# PAGE2_-_MCU.net
KiCad netlist of a schematic drawn in Altium Designer
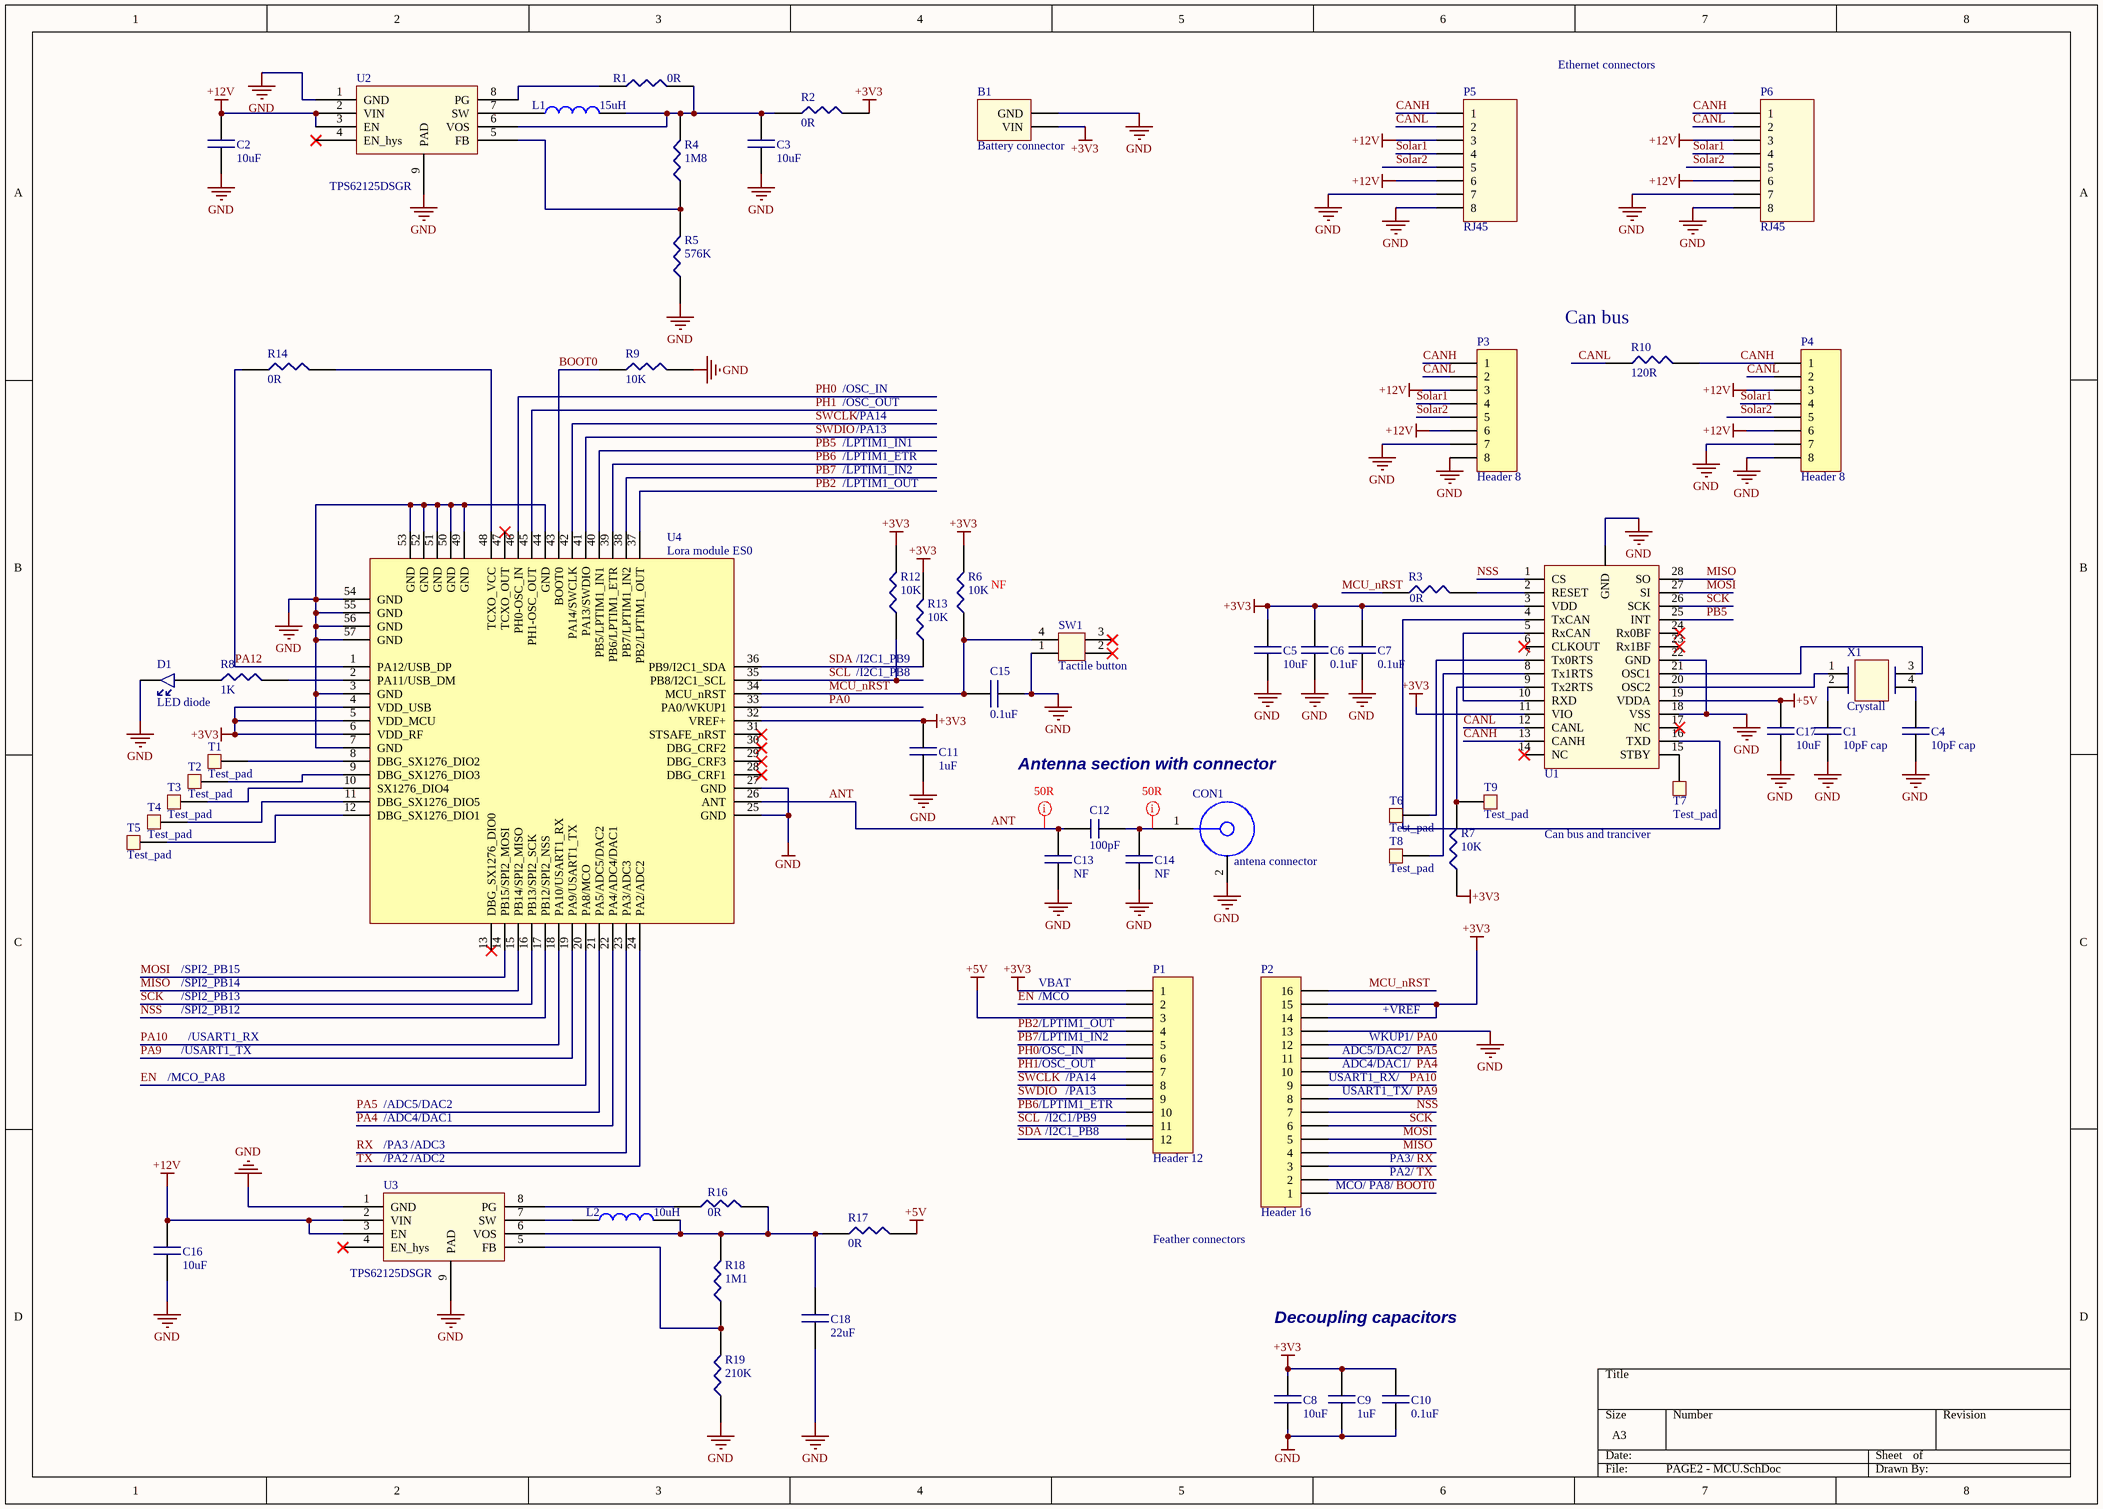
[diagram p0: PAGE2 - MCU.SchDoc]

(export (version "E")
  (design (tool "Eeschema 10.0.6"))
  (components
    (comp (ref "B1")
      (value "Battery connector")
      (footprint "BAT_CON")
      (description "JST-PH 2-Pin SMT Right Angle Breakout Board")
      (fields
        (field (name "MANUFACTURER") "Adafruit Industries")
        (field (name "MANUFACTURER PART NUMBER") "1862")
      )
      (libsource (lib "Lora_feather") (part "1862"))
    )
    (comp (ref "C1")
      (value "10pF cap")
      (footprint "0603Cap")
      (description "Cap Ceramic 10pF 50V X7R 10% SMD 0603 125C T/R")
      (fields
        (field (name "MANUFACTURER") "Kyocera AVX")
        (field (name "MANUFACTURER PART NUMBER") "06035C100KAT2A")
      )
      (libsource (lib "Lora_feather") (part "10pF"))
    )
    (comp (ref "C2")
      (value "10uF")
      (footprint "Lora_feather:0603Cap")
      (fields
        (field (name "MANUFACTURER") "Murata")
        (field (name "MANUFACTURER PART NUMBER") "ZRB18AR61E106ME01L")
        (field (name "TOLERANCE") "±20%")
      )
      (libsource (lib "Lora_feather") (part "10uF Cap"))
    )
    (comp (ref "C3")
      (value "10uF")
      (footprint "Lora_feather:0603Cap")
      (fields
        (field (name "MANUFACTURER") "Murata")
        (field (name "MANUFACTURER PART NUMBER") "ZRB18AR61E106ME01L")
        (field (name "TOLERANCE") "±20%")
      )
      (libsource (lib "Lora_feather") (part "10uF Cap"))
    )
    (comp (ref "C4")
      (value "10pF cap")
      (footprint "0603Cap")
      (description "Cap Ceramic 10pF 50V X7R 10% SMD 0603 125C T/R")
      (fields
        (field (name "MANUFACTURER") "Kyocera AVX")
        (field (name "MANUFACTURER PART NUMBER") "06035C100KAT2A")
      )
      (libsource (lib "Lora_feather") (part "10pF"))
    )
    (comp (ref "C5")
      (value "10uF")
      (footprint "Lora_feather:0603Cap")
      (fields
        (field (name "MANUFACTURER") "Murata")
        (field (name "MANUFACTURER PART NUMBER") "ZRB18AR61E106ME01L")
        (field (name "TOLERANCE") "±20%")
      )
      (libsource (lib "Lora_feather") (part "10uF Cap"))
    )
    (comp (ref "C6")
      (value "0.1uF")
      (footprint "Lora_feather:0603Cap")
      (description "Multilayer Ceramic Capacitors MLCC - SMD/SMT .1uF 50Volts X7R +/-10% 0603 STD")
      (fields
        (field (name "MANUFACTURER") "KEMET")
        (field (name "MANUFACTURER PART NUMBER") "C0603C104K4RAC7081")
      )
      (libsource (lib "Lora_feather") (part "0.1uF"))
    )
    (comp (ref "C7")
      (value "0.1uF")
      (footprint "Lora_feather:0603Cap")
      (description "Multilayer Ceramic Capacitors MLCC - SMD/SMT .1uF 50Volts X7R +/-10% 0603 STD")
      (fields
        (field (name "MANUFACTURER") "KEMET")
        (field (name "MANUFACTURER PART NUMBER") "C0603C104K4RAC7081")
      )
      (libsource (lib "Lora_feather") (part "0.1uF"))
    )
    (comp (ref "C8")
      (value "10uF")
      (footprint "Lora_feather:0603Cap")
      (fields
        (field (name "MANUFACTURER") "Murata")
        (field (name "MANUFACTURER PART NUMBER") "ZRB18AR61E106ME01L")
        (field (name "TOLERANCE") "±20%")
      )
      (libsource (lib "Lora_feather") (part "10uF Cap"))
    )
    (comp (ref "C9")
      (value "1uF")
      (footprint "Lora_feather:0603Cap")
      (description "1µF 50V Ceramic Capacitor X5R 0603 (1608 Metric) 0.063\" L x 0.031\" W (1.60mm x 0.80mm)")
      (fields
        (field (name "MANUFACTURER") "TDK")
        (field (name "MANUFACTURER PART NUMBER") "C1608X5R1E105K080AC")
      )
      (libsource (lib "Lora_feather") (part "1uF"))
    )
    (comp (ref "C10")
      (value "0.1uF")
      (footprint "Lora_feather:0603Cap")
      (description "Multilayer Ceramic Capacitors MLCC - SMD/SMT .1uF 50Volts X7R +/-10% 0603 STD")
      (fields
        (field (name "MANUFACTURER") "KEMET")
        (field (name "MANUFACTURER PART NUMBER") "C0603C104K4RAC7081")
      )
      (libsource (lib "Lora_feather") (part "0.1uF"))
    )
    (comp (ref "C11")
      (value "1uF")
      (footprint "Lora_feather:0603Cap")
      (description "1µF 50V Ceramic Capacitor X5R 0603 (1608 Metric) 0.063\" L x 0.031\" W (1.60mm x 0.80mm)")
      (fields
        (field (name "MANUFACTURER") "TDK")
        (field (name "MANUFACTURER PART NUMBER") "C1608X5R1E105K080AC")
      )
      (libsource (lib "Lora_feather") (part "1uF"))
    )
    (comp (ref "C12")
      (value "100pF")
      (footprint "0402CAP")
      (fields
        (field (name "MANUFACTURER") "Multicomp")
        (field (name "MANUFACTURER PART NUMBER") "MC0402B101K500CT")
      )
      (libsource (lib "Lora_feather") (part "0F"))
    )
    (comp (ref "C13") (value "NF") (footprint "0402CAP") (libsource (lib "Lora_feather") (part "Cap0402")))
    (comp (ref "C14") (value "NF") (footprint "0402CAP") (libsource (lib "Lora_feather") (part "Cap0402")))
    (comp (ref "C15")
      (value "0.1uF")
      (footprint "Lora_feather:0603Cap")
      (description "Multilayer Ceramic Capacitors MLCC - SMD/SMT .1uF 50Volts X7R +/-10% 0603 STD")
      (fields
        (field (name "MANUFACTURER") "KEMET")
        (field (name "MANUFACTURER PART NUMBER") "C0603C104K4RAC7081")
      )
      (libsource (lib "Lora_feather") (part "0.1uF"))
    )
    (comp (ref "C16")
      (value "10uF")
      (footprint "Lora_feather:0603Cap")
      (fields
        (field (name "MANUFACTURER") "Murata")
        (field (name "MANUFACTURER PART NUMBER") "ZRB18AR61E106ME01L")
        (field (name "TOLERANCE") "±20%")
      )
      (libsource (lib "Lora_feather") (part "10uF Cap"))
    )
    (comp (ref "C17")
      (value "10uF")
      (footprint "Lora_feather:0603Cap")
      (fields
        (field (name "MANUFACTURER") "Murata")
        (field (name "MANUFACTURER PART NUMBER") "ZRB18AR61E106ME01L")
        (field (name "TOLERANCE") "±20%")
      )
      (libsource (lib "Lora_feather") (part "10uF Cap"))
    )
    (comp (ref "C18")
      (value "22uF")
      (footprint "0603Cap")
      (fields
        (field (name "MANUFACTURER") "Murata")
        (field (name "MANUFACTURER PART NUMBER") "ZRB18AR60J226ME01L")
        (field (name "TOLERANCE") "±20%")
      )
      (libsource (lib "Lora_feather") (part "22uF"))
    )
    (comp (ref "CON1")
      (value "antena connector")
      (footprint "Lora_feather:uFL SMD CONNECTOR")
      (description "CONN UMC JACK STR 50 OHM SMD")
      (fields
        (field (name "MANUFACTURER") "Hirose")
        (field (name "MANUFACTURER PART NUMBER") "U.FL-R-SMT-1(10)")
      )
      (libsource (lib "Lora_feather") (part "U.FL-R-SMT-1(10)"))
    )
    (comp (ref "D1")
      (value "LED diode")
      (footprint "LED")
      (fields
        (field (name "MANUFACTURER") "Kingbright")
        (field (name "MANUFACTURER PART NUMBER") "KPG1-1608VGC-TT-5MAV")
      )
      (libsource (lib "Lora_feather") (part "LED"))
    )
    (comp (ref "L1")
      (value "15uH")
      (footprint "Lora_feather:Inductor 3.0x2.5")
      (description "Fixed Inductors 15uH 0.28ohms 0.56A")
      (fields
        (field (name "MANUFACTURER") "TDK")
        (field (name "MANUFACTURER PART NUMBER") "VLF302515MT-150M")
      )
      (libsource (lib "Lora_feather") (part "15uH inductor"))
    )
    (comp (ref "L2")
      (value "10uH")
      (footprint "Inductor 3.0x2.5")
      (description "COILCRAFT   LPS3314-103MRB   INDUCTOR, SHLD, 10UH, 20%, 0.65A, SMD")
      (fields
        (field (name "MANUFACTURER") "Coilcraft")
        (field (name "MANUFACTURER PART NUMBER") "LPS3314-103MRB")
      )
      (libsource (lib "Lora_feather") (part "10uH"))
    )
    (comp (ref "P1")
      (value "Header 12")
      (footprint "HDR1X12")
      (description "Header, 12-Pin")
      (fields (field (name "PUBLISHER") "Altium Limited"))
      (libsource (lib "Miscellaneous Connectors") (part "Header 12"))
    )
    (comp (ref "P2")
      (value "Header 16")
      (footprint "HDR1X16")
      (description "Header, 16-Pin")
      (fields (field (name "PUBLISHER") "Altium Limited"))
      (libsource (lib "Miscellaneous Connectors") (part "Header 16"))
    )
    (comp (ref "P3")
      (value "Header 8")
      (footprint "HDR1X8")
      (description "Header, 8-Pin")
      (fields (field (name "PUBLISHER") "Altium Limited"))
      (libsource (lib "Miscellaneous Connectors") (part "Header 8"))
    )
    (comp (ref "P4")
      (value "Header 8")
      (footprint "HDR1X8")
      (description "Header, 8-Pin")
      (fields (field (name "PUBLISHER") "Altium Limited"))
      (libsource (lib "Miscellaneous Connectors") (part "Header 8"))
    )
    (comp (ref "P5")
      (value "RJ45")
      (footprint "EThernet conn")
      (description "MODULAR JACK")
      (fields (field (name "MANUFACTURER") "Molex") (field (name "MANUFACTURER PART NUMBER") "44620-0001"))
      (libsource (lib "Lora_feather") (part "44620-0001"))
    )
    (comp (ref "P6")
      (value "RJ45")
      (footprint "EThernet conn")
      (description "MODULAR JACK")
      (fields (field (name "MANUFACTURER") "Molex") (field (name "MANUFACTURER PART NUMBER") "44620-0001"))
      (libsource (lib "Lora_feather") (part "44620-0001"))
    )
    (comp (ref "R1")
      (value "0R")
      (footprint "Lora_feather:0603Res")
      (description "RES SMD 0.0OHM JUMPER 1/10W 0603")
      (fields
        (field (name "MANUFACTURER") "Vishay")
        (field (name "MANUFACTURER PART NUMBER") "CRCW06030000Z0EA")
      )
      (libsource (lib "Lora_feather") (part "0R"))
    )
    (comp (ref "R2")
      (value "0R")
      (footprint "Lora_feather:0603Res")
      (description "RES SMD 0.0OHM JUMPER 1/10W 0603")
      (fields
        (field (name "MANUFACTURER") "Vishay")
        (field (name "MANUFACTURER PART NUMBER") "CRCW06030000Z0EA")
      )
      (libsource (lib "Lora_feather") (part "0R"))
    )
    (comp (ref "R3")
      (value "0R")
      (footprint "Lora_feather:0603Res")
      (description "RES SMD 0.0OHM JUMPER 1/10W 0603")
      (fields
        (field (name "MANUFACTURER") "Vishay")
        (field (name "MANUFACTURER PART NUMBER") "CRCW06030000Z0EA")
      )
      (libsource (lib "Lora_feather") (part "0R"))
    )
    (comp (ref "R4")
      (value "1M8")
      (footprint "Lora_feather:0603Res")
      (fields
        (field (name "MANUFACTURER") "Multicomp")
        (field (name "MANUFACTURER PART NUMBER") "MCHVR03FTFX1804")
      )
      (libsource (lib "Lora_feather") (part "1.8Mohm Res"))
    )
    (comp (ref "R5")
      (value "576K")
      (footprint "Lora_feather:0603Res")
      (description "Res Thick Film 0603 576K Ohm 1% 0.1W(1/10W) ±100ppm/C Molded SMD Automotive Punched T/R")
      (fields
        (field (name "MANUFACTURER") "Panasonic")
        (field (name "MANUFACTURER PART NUMBER") "ERJ-3EKF5763V")
      )
      (libsource (lib "Lora_feather") (part "576K Res"))
    )
    (comp (ref "R6")
      (value "10K")
      (footprint "Lora_feather:0603Res")
      (fields
        (field (name "MANUFACTURER") "TE Connectivity Neohm")
        (field (name "MANUFACTURER PART NUMBER") "CPF0603F10KC1")
      )
      (libsource (lib "Lora_feather") (part "10K"))
    )
    (comp (ref "R7")
      (value "10K")
      (footprint "Lora_feather:0603Res")
      (fields
        (field (name "MANUFACTURER") "TE Connectivity Neohm")
        (field (name "MANUFACTURER PART NUMBER") "CPF0603F10KC1")
      )
      (libsource (lib "Lora_feather") (part "10K"))
    )
    (comp (ref "R8")
      (value "1K")
      (footprint "0603Res")
      (description "Thick Film Resistors - SMD CRGH0603 1% 1K0 0.2W")
      (fields
        (field (name "MANUFACTURER") "TE Connectivity")
        (field (name "MANUFACTURER PART NUMBER") "CRGH0603F1K0")
      )
      (libsource (lib "Lora_feather") (part "1K"))
    )
    (comp (ref "R9")
      (value "10K")
      (footprint "0603Res")
      (fields
        (field (name "MANUFACTURER") "TE Connectivity Neohm")
        (field (name "MANUFACTURER PART NUMBER") "CPF0603F10KC1")
      )
      (libsource (lib "Lora_feather") (part "10K"))
    )
    (comp (ref "R10")
      (value "120R")
      (footprint "0603Res")
      (description "RES SMD 120 OHM 1% 1/10W 0603")
      (fields
        (field (name "MANUFACTURER") "Vishay")
        (field (name "MANUFACTURER PART NUMBER") "CRCW0603120RFKEA")
      )
      (libsource (lib "Lora_feather") (part "120R"))
    )
    (comp (ref "R12")
      (value "10K")
      (footprint "Lora_feather:0603Res")
      (fields
        (field (name "MANUFACTURER") "TE Connectivity Neohm")
        (field (name "MANUFACTURER PART NUMBER") "CPF0603F10KC1")
      )
      (libsource (lib "Lora_feather") (part "10K"))
    )
    (comp (ref "R13")
      (value "10K")
      (footprint "Lora_feather:0603Res")
      (fields
        (field (name "MANUFACTURER") "TE Connectivity Neohm")
        (field (name "MANUFACTURER PART NUMBER") "CPF0603F10KC1")
      )
      (libsource (lib "Lora_feather") (part "10K"))
    )
    (comp (ref "R14")
      (value "0R")
      (footprint "Lora_feather:0603Res")
      (description "RES SMD 0.0OHM JUMPER 1/10W 0603")
      (fields
        (field (name "MANUFACTURER") "Vishay")
        (field (name "MANUFACTURER PART NUMBER") "CRCW06030000Z0EA")
      )
      (libsource (lib "Lora_feather") (part "0R"))
    )
    (comp (ref "R16")
      (value "0R")
      (footprint "Lora_feather:0603Res")
      (description "RES SMD 0.0OHM JUMPER 1/10W 0603")
      (fields
        (field (name "MANUFACTURER") "Vishay")
        (field (name "MANUFACTURER PART NUMBER") "CRCW06030000Z0EA")
      )
      (libsource (lib "Lora_feather") (part "0R"))
    )
    (comp (ref "R17")
      (value "0R")
      (footprint "Lora_feather:0603Res")
      (description "RES SMD 0.0OHM JUMPER 1/10W 0603")
      (fields
        (field (name "MANUFACTURER") "Vishay")
        (field (name "MANUFACTURER PART NUMBER") "CRCW06030000Z0EA")
      )
      (libsource (lib "Lora_feather") (part "0R"))
    )
    (comp (ref "R18")
      (value "1M1")
      (footprint "0603Res")
      (fields
        (field (name "MANUFACTURER") "Multicomp")
        (field (name "MANUFACTURER PART NUMBER") "MCHVR03FTFX1104")
      )
      (libsource (lib "Lora_feather") (part "1M1"))
    )
    (comp (ref "R19")
      (value "210K")
      (footprint "0603Res")
      (description "Thick Film Resistors - SMD 1/10watt 210Kohms 1%")
      (fields
        (field (name "MANUFACTURER") "Vishay")
        (field (name "MANUFACTURER PART NUMBER") "CRCW0603210KFKEA")
      )
      (libsource (lib "Lora_feather") (part "210K"))
    )
    (comp (ref "SW1")
      (value "Tactile button")
      (footprint "Tactile button")
      (description "SWITCH TACTILE SPST-NO 0.05A 32V")
      (fields (field (name "MANUFACTURER") "ITT C&K") (field (name "MANUFACTURER PART NUMBER") "KMR221NGLFS"))
      (libsource (lib "Lora_feather") (part "KMR221NGLFS"))
    )
    (comp (ref "T1")
      (value "Test_pad")
      (footprint "Test_Pad")
      (description "Test point")
      (libsource (lib "Lora_feather") (part "Test_pad"))
    )
    (comp (ref "T2")
      (value "Test_pad")
      (footprint "Test_Pad")
      (description "Test point")
      (libsource (lib "Lora_feather") (part "Test_pad"))
    )
    (comp (ref "T3")
      (value "Test_pad")
      (footprint "Test_Pad")
      (description "Test point")
      (libsource (lib "Lora_feather") (part "Test_pad"))
    )
    (comp (ref "T4")
      (value "Test_pad")
      (footprint "Test_Pad")
      (description "Test point")
      (libsource (lib "Lora_feather") (part "Test_pad"))
    )
    (comp (ref "T5")
      (value "Test_pad")
      (footprint "Test_Pad")
      (description "Test point")
      (libsource (lib "Lora_feather") (part "Test_pad"))
    )
    (comp (ref "T6")
      (value "Test_pad")
      (footprint "Test_Pad")
      (description "Test point")
      (libsource (lib "Lora_feather") (part "Test_pad"))
    )
    (comp (ref "T7")
      (value "Test_pad")
      (footprint "Test_Pad")
      (description "Test point")
      (libsource (lib "") (part "Test_pad_2"))
    )
    (comp (ref "T8")
      (value "Test_pad")
      (footprint "Test_Pad")
      (description "Test point")
      (libsource (lib "Lora_feather") (part "Test_pad"))
    )
    (comp (ref "T9")
      (value "Test_pad")
      (footprint "Test_Pad")
      (description "Test point")
      (libsource (lib "") (part "Test_pad_1"))
    )
    (comp (ref "U1")
      (value "Can bus and tranciver")
      (footprint "MCP25625")
      (fields
        (field (name "MANUFACTURER") "Microchip")
        (field (name "MANUFACTURER PART NUMBER") "MCP25625-E/ML")
      )
      (libsource (lib "Lora_feather") (part "MCP25625-E/ML"))
    )
    (comp (ref "U2")
      (value "TPS62125DSGR")
      (footprint "Lora_feather:WSON-Voltage regulator")
      (description "Voltage Regulators - Switching Regulators 3V-17V, 300mA Buck Converter")
      (fields (field (name "MANUFACTURER") "Texas Instruments"))
      (libsource (lib "Lora_feather") (part "TPS62125DSGR"))
    )
    (comp (ref "U3")
      (value "TPS62125DSGR")
      (footprint "Lora_feather:WSON-Voltage regulator")
      (description "Voltage Regulators - Switching Regulators 3V-17V, 300mA Buck Converter")
      (fields (field (name "MANUFACTURER") "Texas Instruments"))
      (libsource (lib "Lora_feather") (part "TPS62125DSGR"))
    )
    (comp (ref "U4")
      (value "Lora module ES0")
      (footprint "LORA MODULE ES0")
      (description "Lora Module Murata")
      (libsource (lib "Lora_feather") (part "Lora Module Murata ES0"))
    )
    (comp (ref "X1")
      (value "Crystall")
      (footprint "IQXC-42")
      (fields (field (name "MANUFACTURER") "IQD") (field (name "MANUFACTURER PART NUMBER") "LFXTAL059585"))
      (libsource (lib "Lora_feather") (part "LFXTAL059585"))
    )
  )
  (nets
    (net (code "1") (name "+3V3") (class "Default")
      (node (ref "B1") (pin "1") (pinfunction "VIN_1") (pintype "passive"))
      (node (ref "C10") (pin "2") (pinfunction "2_2") (pintype "passive"))
      (node (ref "C11") (pin "2") (pinfunction "2_2") (pintype "passive"))
      (node (ref "C5") (pin "1") (pinfunction "1_1") (pintype "passive"))
      (node (ref "C6") (pin "2") (pinfunction "2_2") (pintype "passive"))
      (node (ref "C7") (pin "2") (pinfunction "2_2") (pintype "passive"))
      (node (ref "C8") (pin "1") (pinfunction "1_1") (pintype "passive"))
      (node (ref "C9") (pin "1") (pinfunction "1_1") (pintype "passive"))
      (node (ref "P1") (pin "1") (pinfunction "1_1") (pintype "passive"))
      (node (ref "P2") (pin "14") (pinfunction "14_14") (pintype "passive"))
      (node (ref "P2") (pin "15") (pinfunction "15_15") (pintype "passive"))
      (node (ref "R12") (pin "2") (pinfunction "2_2") (pintype "passive"))
      (node (ref "R13") (pin "2") (pinfunction "2_2") (pintype "passive"))
      (node (ref "R2") (pin "2") (pinfunction "2_2") (pintype "passive"))
      (node (ref "R6") (pin "2") (pinfunction "2_2") (pintype "passive"))
      (node (ref "R7") (pin "1") (pinfunction "1_1") (pintype "passive"))
      (node (ref "U1") (pin "11") (pinfunction "VIO_11") (pintype "passive"))
      (node (ref "U1") (pin "3") (pinfunction "VDD_3") (pintype "passive"))
      (node (ref "U4") (pin "32") (pinfunction "VREF+_32") (pintype "passive"))
      (node (ref "U4") (pin "4") (pinfunction "VDD_USB_4") (pintype "passive"))
      (node (ref "U4") (pin "5") (pinfunction "VDD_MCU_5") (pintype "passive"))
      (node (ref "U4") (pin "6") (pinfunction "VDD_RF_6") (pintype "passive"))
    )
    (net (code "2") (name "+5V") (class "Default")
      (node (ref "C17") (pin "1") (pinfunction "1_1") (pintype "passive"))
      (node (ref "P1") (pin "3") (pinfunction "3_3") (pintype "passive"))
      (node (ref "R17") (pin "2") (pinfunction "2_2") (pintype "passive"))
      (node (ref "U1") (pin "19") (pinfunction "VDDA_19") (pintype "passive"))
    )
    (net (code "3") (name "+12V") (class "Default")
      (node (ref "C16") (pin "1") (pinfunction "1_1") (pintype "passive"))
      (node (ref "C2") (pin "1") (pinfunction "1_1") (pintype "passive"))
      (node (ref "P3") (pin "3") (pinfunction "3_3") (pintype "passive"))
      (node (ref "P3") (pin "6") (pinfunction "6_6") (pintype "passive"))
      (node (ref "P4") (pin "3") (pinfunction "3_3") (pintype "passive"))
      (node (ref "P4") (pin "6") (pinfunction "6_6") (pintype "passive"))
      (node (ref "P5") (pin "3") (pinfunction "3_3") (pintype "passive"))
      (node (ref "P5") (pin "6") (pinfunction "6_6") (pintype "passive"))
      (node (ref "P6") (pin "3") (pinfunction "3_3") (pintype "passive"))
      (node (ref "P6") (pin "6") (pinfunction "6_6") (pintype "passive"))
      (node (ref "U2") (pin "2") (pinfunction "VIN_2") (pintype "passive"))
      (node (ref "U2") (pin "3") (pinfunction "EN_3") (pintype "passive"))
      (node (ref "U3") (pin "2") (pinfunction "VIN_2") (pintype "passive"))
      (node (ref "U3") (pin "3") (pinfunction "EN_3") (pintype "passive"))
    )
    (net (code "4") (name "/ANT") (class "Default")
      (node (ref "C12") (pin "1") (pinfunction "1_1") (pintype "passive"))
      (node (ref "C13") (pin "2") (pinfunction "2_2") (pintype "passive"))
      (node (ref "U4") (pin "26") (pinfunction "ANT_26") (pintype "passive"))
    )
    (net (code "5") (name "/BOOT0") (class "Default")
      (node (ref "P2") (pin "1") (pinfunction "1_1") (pintype "passive"))
      (node (ref "R9") (pin "1") (pinfunction "1_1") (pintype "passive"))
      (node (ref "U4") (pin "43") (pinfunction "BOOT0_43") (pintype "passive"))
    )
    (net (code "6") (name "/CANH") (class "Default")
      (node (ref "P3") (pin "1") (pinfunction "1_1") (pintype "passive"))
      (node (ref "P4") (pin "1") (pinfunction "1_1") (pintype "passive"))
      (node (ref "P5") (pin "1") (pinfunction "1_1") (pintype "passive"))
      (node (ref "P6") (pin "1") (pinfunction "1_1") (pintype "passive"))
      (node (ref "R10") (pin "2") (pinfunction "2_2") (pintype "passive"))
      (node (ref "U1") (pin "13") (pinfunction "CANH_13") (pintype "passive"))
    )
    (net (code "7") (name "/CANL") (class "Default")
      (node (ref "P3") (pin "2") (pinfunction "2_2") (pintype "passive"))
      (node (ref "P4") (pin "2") (pinfunction "2_2") (pintype "passive"))
      (node (ref "P5") (pin "2") (pinfunction "2_2") (pintype "passive"))
      (node (ref "P6") (pin "2") (pinfunction "2_2") (pintype "passive"))
      (node (ref "R10") (pin "1") (pinfunction "1_1") (pintype "passive"))
      (node (ref "U1") (pin "12") (pinfunction "CANL_12") (pintype "passive"))
    )
    (net (code "8") (name "/EN") (class "Default")
      (node (ref "P1") (pin "2") (pinfunction "2_2") (pintype "passive"))
      (node (ref "U4") (pin "20") (pinfunction "PA8/MCO_20") (pintype "passive"))
    )
    (net (code "9") (name "/MCU_nRST") (class "Default")
      (node (ref "C15") (pin "1") (pinfunction "1_1") (pintype "passive"))
      (node (ref "P2") (pin "16") (pinfunction "16_16") (pintype "passive"))
      (node (ref "R3") (pin "1") (pinfunction "1_1") (pintype "passive"))
      (node (ref "R6") (pin "1") (pinfunction "1_1") (pintype "passive"))
      (node (ref "SW1") (pin "4") (pinfunction "4_4") (pintype "passive"))
      (node (ref "U4") (pin "34") (pinfunction "MCU_nRST_34") (pintype "passive"))
    )
    (net (code "10") (name "/MISO") (class "Default")
      (node (ref "P2") (pin "4") (pinfunction "4_4") (pintype "passive"))
      (node (ref "U1") (pin "28") (pinfunction "SO_28") (pintype "passive"))
      (node (ref "U4") (pin "15") (pinfunction "PB14/SPI2_MISO_15") (pintype "passive"))
    )
    (net (code "11") (name "/MOSI") (class "Default")
      (node (ref "P2") (pin "5") (pinfunction "5_5") (pintype "passive"))
      (node (ref "U1") (pin "27") (pinfunction "SI_27") (pintype "passive"))
      (node (ref "U4") (pin "14") (pinfunction "PB15/SPI2_MOSI_14") (pintype "passive"))
    )
    (net (code "12") (name "/NSS") (class "Default")
      (node (ref "P2") (pin "7") (pinfunction "7_7") (pintype "passive"))
      (node (ref "U1") (pin "1") (pinfunction "CS_1") (pintype "passive"))
      (node (ref "U4") (pin "17") (pinfunction "PB12/SPI2_NSS_17") (pintype "passive"))
    )
    (net (code "13") (name "/PA0") (class "Default")
      (node (ref "P2") (pin "12") (pinfunction "12_12") (pintype "passive"))
      (node (ref "U4") (pin "33") (pinfunction "PA0/WKUP1_33") (pintype "passive"))
    )
    (net (code "14") (name "/PA4") (class "Default")
      (node (ref "P2") (pin "10") (pinfunction "10_10") (pintype "passive"))
      (node (ref "U4") (pin "22") (pinfunction "PA4/ADC4/DAC1_22") (pintype "passive"))
    )
    (net (code "15") (name "/PA5") (class "Default")
      (node (ref "P2") (pin "11") (pinfunction "11_11") (pintype "passive"))
      (node (ref "U4") (pin "21") (pinfunction "PA5/ADC5/DAC2_21") (pintype "passive"))
    )
    (net (code "16") (name "/PA9") (class "Default")
      (node (ref "P2") (pin "8") (pinfunction "8_8") (pintype "passive"))
      (node (ref "U4") (pin "19") (pinfunction "PA9/USART1_TX_19") (pintype "passive"))
    )
    (net (code "17") (name "/PA10") (class "Default")
      (node (ref "P2") (pin "9") (pinfunction "9_9") (pintype "passive"))
      (node (ref "U4") (pin "18") (pinfunction "PA10/USART1_RX_18") (pintype "passive"))
    )
    (net (code "18") (name "/PA12") (class "Default")
      (node (ref "R14") (pin "1") (pinfunction "1_1") (pintype "passive"))
      (node (ref "U4") (pin "1") (pinfunction "PA12/USB_DP_1") (pintype "passive"))
    )
    (net (code "19") (name "/PB2") (class "Default")
      (node (ref "P1") (pin "4") (pinfunction "4_4") (pintype "passive"))
      (node (ref "U4") (pin "37") (pinfunction "PB2/LPTIM1_OUT_37") (pintype "passive"))
    )
    (net (code "20") (name "/PB5") (class "Default")
      (node (ref "U1") (pin "25") (pinfunction "INT_25") (pintype "passive"))
      (node (ref "U4") (pin "40") (pinfunction "PB5/LPTIM1_IN1_40") (pintype "passive"))
    )
    (net (code "21") (name "/PB6") (class "Default")
      (node (ref "P1") (pin "10") (pinfunction "10_10") (pintype "passive"))
      (node (ref "U4") (pin "39") (pinfunction "PB6/LPTIM1_ETR_39") (pintype "passive"))
    )
    (net (code "22") (name "/PB7") (class "Default")
      (node (ref "P1") (pin "5") (pinfunction "5_5") (pintype "passive"))
      (node (ref "U4") (pin "38") (pinfunction "PB7/LPTIM1_IN2_38") (pintype "passive"))
    )
    (net (code "23") (name "/PH0") (class "Default")
      (node (ref "P1") (pin "6") (pinfunction "6_6") (pintype "passive"))
      (node (ref "U4") (pin "46") (pinfunction "PH0-OSC_IN_46") (pintype "passive"))
    )
    (net (code "24") (name "/PH1") (class "Default")
      (node (ref "P1") (pin "7") (pinfunction "7_7") (pintype "passive"))
      (node (ref "U4") (pin "45") (pinfunction "PH1-OSC_OUT_45") (pintype "passive"))
    )
    (net (code "25") (name "/RX") (class "Default")
      (node (ref "P2") (pin "3") (pinfunction "3_3") (pintype "passive"))
      (node (ref "U4") (pin "23") (pinfunction "PA3/ADC3_23") (pintype "passive"))
    )
    (net (code "26") (name "/SCK") (class "Default")
      (node (ref "P2") (pin "6") (pinfunction "6_6") (pintype "passive"))
      (node (ref "U1") (pin "26") (pinfunction "SCK_26") (pintype "passive"))
      (node (ref "U4") (pin "16") (pinfunction "PB13/SPI2_SCK_16") (pintype "passive"))
    )
    (net (code "27") (name "/SCL") (class "Default")
      (node (ref "P1") (pin "11") (pinfunction "11_11") (pintype "passive"))
      (node (ref "R12") (pin "1") (pinfunction "1_1") (pintype "passive"))
      (node (ref "U4") (pin "35") (pinfunction "PB8/I2C1_SCL_35") (pintype "passive"))
    )
    (net (code "28") (name "/SDA") (class "Default")
      (node (ref "P1") (pin "12") (pinfunction "12_12") (pintype "passive"))
      (node (ref "R13") (pin "1") (pinfunction "1_1") (pintype "passive"))
      (node (ref "U4") (pin "36") (pinfunction "PB9/I2C1_SDA_36") (pintype "passive"))
    )
    (net (code "29") (name "/SWCLK") (class "Default")
      (node (ref "P1") (pin "8") (pinfunction "8_8") (pintype "passive"))
      (node (ref "U4") (pin "42") (pinfunction "PA14/SWCLK_42") (pintype "passive"))
    )
    (net (code "30") (name "/SWDIO") (class "Default")
      (node (ref "P1") (pin "9") (pinfunction "9_9") (pintype "passive"))
      (node (ref "U4") (pin "41") (pinfunction "PA13/SWDIO_41") (pintype "passive"))
    )
    (net (code "31") (name "/Solar1") (class "Default")
      (node (ref "P3") (pin "4") (pinfunction "4_4") (pintype "passive"))
      (node (ref "P4") (pin "4") (pinfunction "4_4") (pintype "passive"))
      (node (ref "P5") (pin "4") (pinfunction "4_4") (pintype "passive"))
      (node (ref "P6") (pin "4") (pinfunction "4_4") (pintype "passive"))
    )
    (net (code "32") (name "/Solar2") (class "Default")
      (node (ref "P3") (pin "5") (pinfunction "5_5") (pintype "passive"))
      (node (ref "P4") (pin "5") (pinfunction "5_5") (pintype "passive"))
      (node (ref "P5") (pin "5") (pinfunction "5_5") (pintype "passive"))
      (node (ref "P6") (pin "5") (pinfunction "5_5") (pintype "passive"))
    )
    (net (code "33") (name "/TX") (class "Default")
      (node (ref "P2") (pin "2") (pinfunction "2_2") (pintype "passive"))
      (node (ref "U4") (pin "24") (pinfunction "PA2/ADC2_24") (pintype "passive"))
    )
    (net (code "34") (name "GND") (class "Default")
      (node (ref "B1") (pin "2") (pinfunction "GND_2") (pintype "passive"))
      (node (ref "C1") (pin "1") (pinfunction "1_1") (pintype "passive"))
      (node (ref "C10") (pin "1") (pinfunction "1_1") (pintype "passive"))
      (node (ref "C11") (pin "1") (pinfunction "1_1") (pintype "passive"))
      (node (ref "C13") (pin "1") (pinfunction "1_1") (pintype "passive"))
      (node (ref "C14") (pin "1") (pinfunction "1_1") (pintype "passive"))
      (node (ref "C15") (pin "2") (pinfunction "2_2") (pintype "passive"))
      (node (ref "C16") (pin "2") (pinfunction "2_2") (pintype "passive"))
      (node (ref "C17") (pin "2") (pinfunction "2_2") (pintype "passive"))
      (node (ref "C18") (pin "1") (pinfunction "1_1") (pintype "passive"))
      (node (ref "C2") (pin "2") (pinfunction "2_2") (pintype "passive"))
      (node (ref "C3") (pin "2") (pinfunction "2_2") (pintype "passive"))
      (node (ref "C4") (pin "1") (pinfunction "1_1") (pintype "passive"))
      (node (ref "C5") (pin "2") (pinfunction "2_2") (pintype "passive"))
      (node (ref "C6") (pin "1") (pinfunction "1_1") (pintype "passive"))
      (node (ref "C7") (pin "1") (pinfunction "1_1") (pintype "passive"))
      (node (ref "C8") (pin "2") (pinfunction "2_2") (pintype "passive"))
      (node (ref "C9") (pin "2") (pinfunction "2_2") (pintype "passive"))
      (node (ref "CON1") (pin "2") (pinfunction "2_2") (pintype "open_collector"))
      (node (ref "D1") (pin "1") (pinfunction "1_1") (pintype "passive"))
      (node (ref "P2") (pin "13") (pinfunction "13_13") (pintype "passive"))
      (node (ref "P3") (pin "7") (pinfunction "7_7") (pintype "passive"))
      (node (ref "P3") (pin "8") (pinfunction "8_8") (pintype "passive"))
      (node (ref "P4") (pin "7") (pinfunction "7_7") (pintype "passive"))
      (node (ref "P4") (pin "8") (pinfunction "8_8") (pintype "passive"))
      (node (ref "P5") (pin "7") (pinfunction "7_7") (pintype "passive"))
      (node (ref "P5") (pin "8") (pinfunction "8_8") (pintype "passive"))
      (node (ref "P6") (pin "7") (pinfunction "7_7") (pintype "passive"))
      (node (ref "P6") (pin "8") (pinfunction "8_8") (pintype "passive"))
      (node (ref "R19") (pin "1") (pinfunction "1_1") (pintype "passive"))
      (node (ref "R5") (pin "1") (pinfunction "1_1") (pintype "passive"))
      (node (ref "R9") (pin "2") (pinfunction "2_2") (pintype "passive"))
      (node (ref "SW1") (pin "1") (pinfunction "1_1") (pintype "passive"))
      (node (ref "U1") (pin "18") (pinfunction "VSS_18") (pintype "passive"))
      (node (ref "U1") (pin "22") (pinfunction "GND_22") (pintype "passive"))
      (node (ref "U1") (pin "29") (pinfunction "GND_29") (pintype "passive"))
      (node (ref "U2") (pin "1") (pinfunction "GND_1") (pintype "passive"))
      (node (ref "U2") (pin "9") (pinfunction "PAD_9") (pintype "passive"))
      (node (ref "U3") (pin "1") (pinfunction "GND_1") (pintype "passive"))
      (node (ref "U3") (pin "9") (pinfunction "PAD_9") (pintype "passive"))
      (node (ref "U4") (pin "25") (pinfunction "GND_25") (pintype "passive"))
      (node (ref "U4") (pin "27") (pinfunction "GND_27") (pintype "passive"))
      (node (ref "U4") (pin "3") (pinfunction "GND_3") (pintype "passive"))
      (node (ref "U4") (pin "44") (pinfunction "GND_44") (pintype "passive"))
      (node (ref "U4") (pin "49") (pinfunction "GND_49") (pintype "passive"))
      (node (ref "U4") (pin "50") (pinfunction "GND_50") (pintype "passive"))
      (node (ref "U4") (pin "51") (pinfunction "GND_51") (pintype "passive"))
      (node (ref "U4") (pin "52") (pinfunction "GND_52") (pintype "passive"))
      (node (ref "U4") (pin "53") (pinfunction "GND_53") (pintype "passive"))
      (node (ref "U4") (pin "54") (pinfunction "GND_54") (pintype "passive"))
      (node (ref "U4") (pin "55") (pinfunction "GND_55") (pintype "passive"))
      (node (ref "U4") (pin "56") (pinfunction "GND_56") (pintype "passive"))
      (node (ref "U4") (pin "57") (pinfunction "GND_57") (pintype "passive"))
      (node (ref "U4") (pin "7") (pinfunction "GND_7") (pintype "passive"))
    )
    (net (code "35") (name "Net-(C1-Pad2)") (class "Default")
      (node (ref "C1") (pin "2") (pinfunction "2_2") (pintype "passive"))
      (node (ref "X1") (pin "2") (pinfunction "2_2") (pintype "passive"))
    )
    (net (code "36") (name "Net-(C4-Pad2)") (class "Default")
      (node (ref "C4") (pin "2") (pinfunction "2_2") (pintype "passive"))
      (node (ref "X1") (pin "4") (pinfunction "4_4") (pintype "passive"))
    )
    (net (code "37") (name "Net-(C12-Pad2)") (class "Default")
      (node (ref "C12") (pin "2") (pinfunction "2_2") (pintype "passive"))
      (node (ref "C14") (pin "2") (pinfunction "2_2") (pintype "passive"))
      (node (ref "CON1") (pin "1") (pinfunction "1_1") (pintype "open_collector"))
    )
    (net (code "38") (name "Net-(D1-Pad2)") (class "Default")
      (node (ref "D1") (pin "2") (pinfunction "2_2") (pintype "passive"))
      (node (ref "R8") (pin "1") (pinfunction "1_1") (pintype "passive"))
    )
    (net (code "39") (name "Net-(U1-OSC1)") (class "Default")
      (node (ref "U1") (pin "21") (pinfunction "OSC1_21") (pintype "passive"))
      (node (ref "X1") (pin "3") (pinfunction "3_3") (pintype "passive"))
    )
    (net (code "40") (name "Net-(U1-OSC2)") (class "Default")
      (node (ref "U1") (pin "20") (pinfunction "OSC2_20") (pintype "passive"))
      (node (ref "X1") (pin "1") (pinfunction "1_1") (pintype "passive"))
    )
    (net (code "41") (name "Net-(U1-RESET)") (class "Default")
      (node (ref "R3") (pin "2") (pinfunction "2_2") (pintype "passive"))
      (node (ref "U1") (pin "2") (pinfunction "RESET_2") (pintype "passive"))
    )
    (net (code "42") (name "Net-(U1-RXD)") (class "Default")
      (node (ref "U1") (pin "10") (pinfunction "RXD_10") (pintype "passive"))
      (node (ref "U1") (pin "5") (pinfunction "RxCAN_5") (pintype "passive"))
    )
    (net (code "43") (name "Net-(U1-STBY)") (class "Default")
      (node (ref "T7") (pin "1") (pinfunction "1_1") (pintype "passive"))
      (node (ref "U1") (pin "15") (pinfunction "STBY_15") (pintype "passive"))
    )
    (net (code "44") (name "Net-(U1-TXD)") (class "Default")
      (node (ref "U1") (pin "16") (pinfunction "TXD_16") (pintype "passive"))
      (node (ref "U1") (pin "4") (pinfunction "TxCAN_4") (pintype "passive"))
    )
    (net (code "45") (name "Net-(U1-Tx0RTS)") (class "Default")
      (node (ref "T6") (pin "1") (pinfunction "1_1") (pintype "passive"))
      (node (ref "U1") (pin "7") (pinfunction "Tx0RTS_7") (pintype "passive"))
    )
    (net (code "46") (name "Net-(U1-Tx1RTS)") (class "Default")
      (node (ref "T8") (pin "1") (pinfunction "1_1") (pintype "passive"))
      (node (ref "U1") (pin "8") (pinfunction "Tx1RTS_8") (pintype "passive"))
    )
    (net (code "47") (name "Net-(U1-Tx2RTS)") (class "Default")
      (node (ref "R7") (pin "2") (pinfunction "2_2") (pintype "passive"))
      (node (ref "T9") (pin "1") (pinfunction "1_1") (pintype "passive"))
      (node (ref "U1") (pin "9") (pinfunction "Tx2RTS_9") (pintype "passive"))
    )
    (net (code "48") (name "Net-(U2-FB)") (class "Default")
      (node (ref "R4") (pin "1") (pinfunction "1_1") (pintype "passive"))
      (node (ref "R5") (pin "2") (pinfunction "2_2") (pintype "passive"))
      (node (ref "U2") (pin "5") (pinfunction "FB_5") (pintype "passive"))
    )
    (net (code "49") (name "Net-(U2-PG)") (class "Default")
      (node (ref "R1") (pin "1") (pinfunction "1_1") (pintype "passive"))
      (node (ref "U2") (pin "8") (pinfunction "PG_8") (pintype "passive"))
    )
    (net (code "50") (name "Net-(U2-SW)") (class "Default")
      (node (ref "L1") (pin "1") (pinfunction "1_1") (pintype "passive"))
      (node (ref "U2") (pin "7") (pinfunction "SW_7") (pintype "passive"))
    )
    (net (code "51") (name "Net-(U2-VOS)") (class "Default")
      (node (ref "C3") (pin "1") (pinfunction "1_1") (pintype "passive"))
      (node (ref "L1") (pin "2") (pinfunction "2_2") (pintype "passive"))
      (node (ref "R1") (pin "2") (pinfunction "2_2") (pintype "passive"))
      (node (ref "R2") (pin "1") (pinfunction "1_1") (pintype "passive"))
      (node (ref "R4") (pin "2") (pinfunction "2_2") (pintype "passive"))
      (node (ref "U2") (pin "6") (pinfunction "VOS_6") (pintype "passive"))
    )
    (net (code "52") (name "Net-(U3-FB)") (class "Default")
      (node (ref "R18") (pin "1") (pinfunction "1_1") (pintype "passive"))
      (node (ref "R19") (pin "2") (pinfunction "2_2") (pintype "passive"))
      (node (ref "U3") (pin "5") (pinfunction "FB_5") (pintype "passive"))
    )
    (net (code "53") (name "Net-(U3-PG)") (class "Default")
      (node (ref "R16") (pin "1") (pinfunction "1_1") (pintype "passive"))
      (node (ref "U3") (pin "8") (pinfunction "PG_8") (pintype "passive"))
    )
    (net (code "54") (name "Net-(U3-SW)") (class "Default")
      (node (ref "L2") (pin "1") (pinfunction "1_1") (pintype "passive"))
      (node (ref "U3") (pin "7") (pinfunction "SW_7") (pintype "passive"))
    )
    (net (code "55") (name "Net-(U3-VOS)") (class "Default")
      (node (ref "C18") (pin "2") (pinfunction "2_2") (pintype "passive"))
      (node (ref "L2") (pin "2") (pinfunction "2_2") (pintype "passive"))
      (node (ref "R16") (pin "2") (pinfunction "2_2") (pintype "passive"))
      (node (ref "R17") (pin "1") (pinfunction "1_1") (pintype "passive"))
      (node (ref "R18") (pin "2") (pinfunction "2_2") (pintype "passive"))
      (node (ref "U3") (pin "6") (pinfunction "VOS_6") (pintype "passive"))
    )
    (net (code "56") (name "Net-(U4-DBG_SX1276_DIO1)") (class "Default")
      (node (ref "T5") (pin "1") (pinfunction "1_1") (pintype "passive"))
      (node (ref "U4") (pin "12") (pinfunction "DBG_SX1276_DIO1_12") (pintype "passive"))
    )
    (net (code "57") (name "Net-(U4-DBG_SX1276_DIO2)") (class "Default")
      (node (ref "T1") (pin "1") (pinfunction "1_1") (pintype "passive"))
      (node (ref "U4") (pin "8") (pinfunction "DBG_SX1276_DIO2_8") (pintype "passive"))
    )
    (net (code "58") (name "Net-(U4-DBG_SX1276_DIO3)") (class "Default")
      (node (ref "T2") (pin "1") (pinfunction "1_1") (pintype "passive"))
      (node (ref "U4") (pin "9") (pinfunction "DBG_SX1276_DIO3_9") (pintype "passive"))
    )
    (net (code "59") (name "Net-(U4-DBG_SX1276_DIO5)") (class "Default")
      (node (ref "T4") (pin "1") (pinfunction "1_1") (pintype "passive"))
      (node (ref "U4") (pin "11") (pinfunction "DBG_SX1276_DIO5_11") (pintype "passive"))
    )
    (net (code "60") (name "Net-(U4-PA11{slash}USB_DM)") (class "Default")
      (node (ref "R8") (pin "2") (pinfunction "2_2") (pintype "passive"))
      (node (ref "U4") (pin "2") (pinfunction "PA11/USB_DM_2") (pintype "passive"))
    )
    (net (code "61") (name "Net-(U4-SX1276_DIO4)") (class "Default")
      (node (ref "T3") (pin "1") (pinfunction "1_1") (pintype "passive"))
      (node (ref "U4") (pin "10") (pinfunction "SX1276_DIO4_10") (pintype "passive"))
    )
    (net (code "62") (name "Net-(U4-TCXO_VCC)") (class "Default")
      (node (ref "R14") (pin "2") (pinfunction "2_2") (pintype "passive"))
      (node (ref "U4") (pin "48") (pinfunction "TCXO_VCC_48") (pintype "passive"))
    )
    (net (code "63") (name "unconnected-(SW1-Pad2)") (class "Default")
      (node (ref "SW1") (pin "2") (pinfunction "2_2") (pintype "passive+no_connect"))
    )
    (net (code "64") (name "unconnected-(SW1-Pad3)") (class "Default")
      (node (ref "SW1") (pin "3") (pinfunction "3_3") (pintype "passive+no_connect"))
    )
    (net (code "65") (name "unconnected-(U1-CLKOUT-Pad6)") (class "Default")
      (node (ref "U1") (pin "6") (pinfunction "CLKOUT_6") (pintype "passive+no_connect"))
    )
    (net (code "66") (name "unconnected-(U1-NC-Pad14)") (class "Default")
      (node (ref "U1") (pin "14") (pinfunction "NC_14") (pintype "passive+no_connect"))
    )
    (net (code "67") (name "unconnected-(U1-NC-Pad17)") (class "Default")
      (node (ref "U1") (pin "17") (pinfunction "NC_17") (pintype "passive+no_connect"))
    )
    (net (code "68") (name "unconnected-(U1-Rx0BF-Pad24)") (class "Default")
      (node (ref "U1") (pin "24") (pinfunction "Rx0BF_24") (pintype "passive+no_connect"))
    )
    (net (code "69") (name "unconnected-(U1-Rx1BF-Pad23)") (class "Default")
      (node (ref "U1") (pin "23") (pinfunction "Rx1BF_23") (pintype "passive+no_connect"))
    )
    (net (code "70") (name "unconnected-(U2-EN_hys-Pad4)") (class "Default")
      (node (ref "U2") (pin "4") (pinfunction "EN_hys_4") (pintype "passive+no_connect"))
    )
    (net (code "71") (name "unconnected-(U3-EN_hys-Pad4)") (class "Default")
      (node (ref "U3") (pin "4") (pinfunction "EN_hys_4") (pintype "passive+no_connect"))
    )
    (net (code "72") (name "unconnected-(U4-DBG_CRF1-Pad28)") (class "Default")
      (node (ref "U4") (pin "28") (pinfunction "DBG_CRF1_28") (pintype "passive+no_connect"))
    )
    (net (code "73") (name "unconnected-(U4-DBG_CRF2-Pad30)") (class "Default")
      (node (ref "U4") (pin "30") (pinfunction "DBG_CRF2_30") (pintype "passive+no_connect"))
    )
    (net (code "74") (name "unconnected-(U4-DBG_CRF3-Pad29)") (class "Default")
      (node (ref "U4") (pin "29") (pinfunction "DBG_CRF3_29") (pintype "passive+no_connect"))
    )
    (net (code "75") (name "unconnected-(U4-DBG_SX1276_DIO0-Pad13)") (class "Default")
      (node (ref "U4") (pin "13") (pinfunction "DBG_SX1276_DIO0_13") (pintype "passive+no_connect"))
    )
    (net (code "76") (name "unconnected-(U4-STSAFE_nRST-Pad31)") (class "Default")
      (node (ref "U4") (pin "31") (pinfunction "STSAFE_nRST_31") (pintype "passive+no_connect"))
    )
    (net (code "77") (name "unconnected-(U4-TCXO_OUT-Pad47)") (class "Default")
      (node (ref "U4") (pin "47") (pinfunction "TCXO_OUT_47") (pintype "passive+no_connect"))
    )
  )
)
